# Frame_Diagram.net
KiCad netlist of a schematic drawn in EAGLE
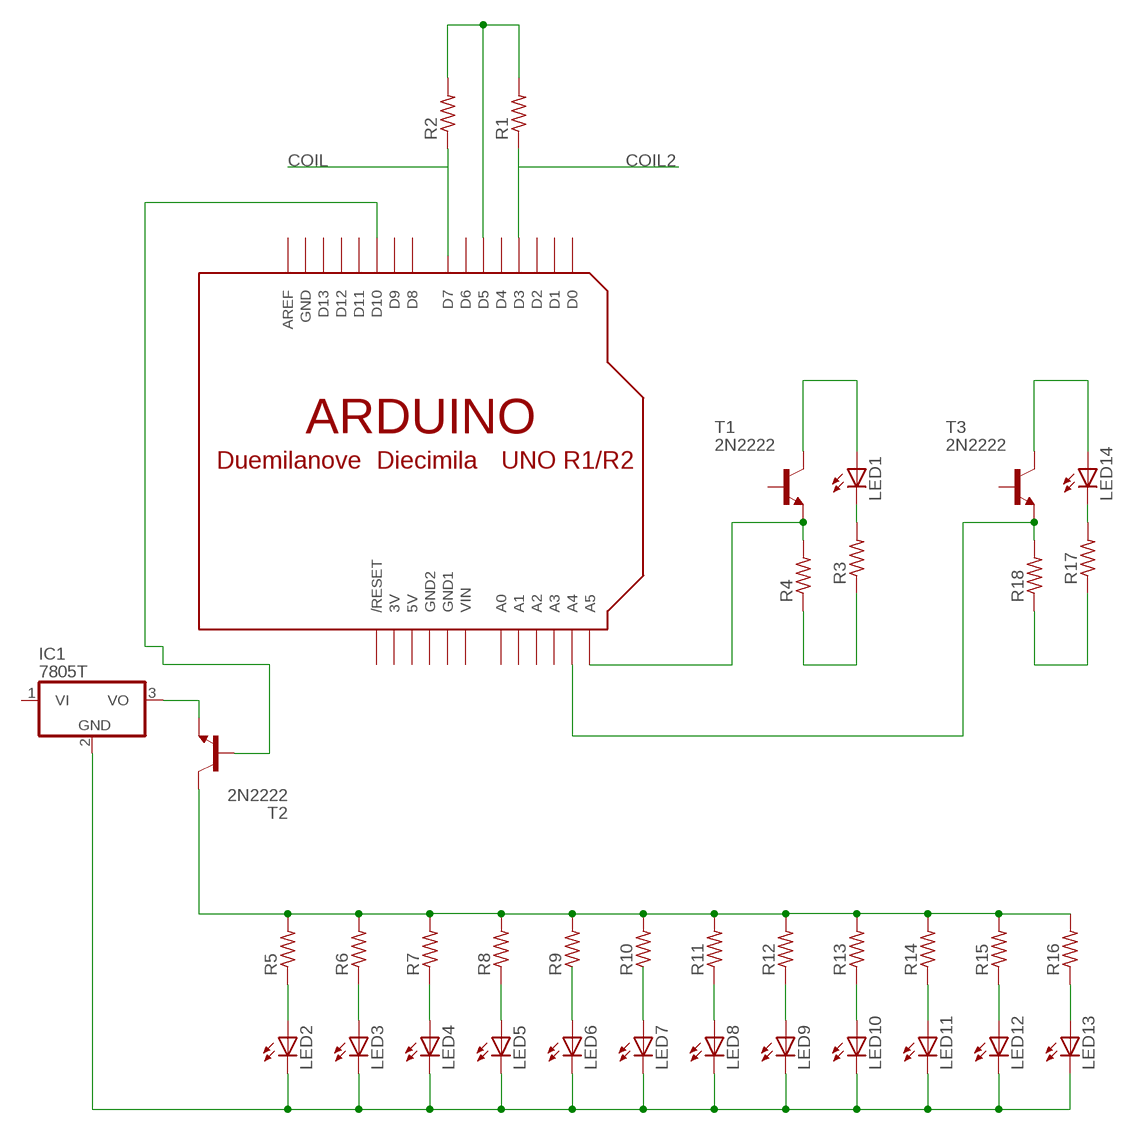
[diagram p0: schematic, sheet 1]

(export (version "E")
  (design (tool "Eeschema 10.0.6"))
  (components
    (comp (ref "IC1")
      (value "7805T")
      (footprint "eagle-import:TO220H")
      (libsource (lib "eagle-import") (part "78T05"))
    )
    (comp (ref "LED1")
      (value "LED")
      (footprint "eagle-import:SMARTLED-TTW")
      (libsource (lib "eagle-import") (part "LED"))
    )
    (comp (ref "LED2")
      (value "LEDLD260")
      (footprint "eagle-import:LD260")
      (libsource (lib "eagle-import") (part "LEDLD260"))
    )
    (comp (ref "LED3")
      (value "LEDLD260")
      (footprint "eagle-import:LD260")
      (libsource (lib "eagle-import") (part "LEDLD260"))
    )
    (comp (ref "LED4")
      (value "LEDLD260")
      (footprint "eagle-import:LD260")
      (libsource (lib "eagle-import") (part "LEDLD260"))
    )
    (comp (ref "LED5")
      (value "LEDLD260")
      (footprint "eagle-import:LD260")
      (libsource (lib "eagle-import") (part "LEDLD260"))
    )
    (comp (ref "LED6")
      (value "LEDLD260")
      (footprint "eagle-import:LD260")
      (libsource (lib "eagle-import") (part "LEDLD260"))
    )
    (comp (ref "LED7")
      (value "LEDLD260")
      (footprint "eagle-import:LD260")
      (libsource (lib "eagle-import") (part "LEDLD260"))
    )
    (comp (ref "LED8")
      (value "LEDLD260")
      (footprint "eagle-import:LD260")
      (libsource (lib "eagle-import") (part "LEDLD260"))
    )
    (comp (ref "LED9")
      (value "LEDLD260")
      (footprint "eagle-import:LD260")
      (libsource (lib "eagle-import") (part "LEDLD260"))
    )
    (comp (ref "LED10")
      (value "LEDLD260")
      (footprint "eagle-import:LD260")
      (libsource (lib "eagle-import") (part "LEDLD260"))
    )
    (comp (ref "LED11")
      (value "LEDLD260")
      (footprint "eagle-import:LD260")
      (libsource (lib "eagle-import") (part "LEDLD260"))
    )
    (comp (ref "LED12")
      (value "LEDLD260")
      (footprint "eagle-import:LD260")
      (libsource (lib "eagle-import") (part "LEDLD260"))
    )
    (comp (ref "LED13")
      (value "LEDLD260")
      (footprint "eagle-import:LD260")
      (libsource (lib "eagle-import") (part "LEDLD260"))
    )
    (comp (ref "LED14")
      (value "LED")
      (footprint "eagle-import:SMARTLED-TTW")
      (libsource (lib "eagle-import") (part "LED"))
    )
    (comp (ref "R1")
      (value "R-US_0204/7")
      (footprint "eagle-import:0204_7")
      (libsource (lib "eagle-import") (part "R-US_0204/7"))
    )
    (comp (ref "R2")
      (value "R-US_0204/7")
      (footprint "eagle-import:0204_7")
      (libsource (lib "eagle-import") (part "R-US_0204/7"))
    )
    (comp (ref "R3")
      (value "R-US_0204/7")
      (footprint "eagle-import:0204_7")
      (libsource (lib "eagle-import") (part "R-US_0204/7"))
    )
    (comp (ref "R4")
      (value "R-US_0204/7")
      (footprint "eagle-import:0204_7")
      (libsource (lib "eagle-import") (part "R-US_0204/7"))
    )
    (comp (ref "R5")
      (value "R-US_0204/5")
      (footprint "eagle-import:0204_5")
      (libsource (lib "eagle-import") (part "R-US_0204/5"))
    )
    (comp (ref "R6")
      (value "R-US_0204/5")
      (footprint "eagle-import:0204_5")
      (libsource (lib "eagle-import") (part "R-US_0204/5"))
    )
    (comp (ref "R7")
      (value "R-US_0204/5")
      (footprint "eagle-import:0204_5")
      (libsource (lib "eagle-import") (part "R-US_0204/5"))
    )
    (comp (ref "R8")
      (value "R-US_0204/5")
      (footprint "eagle-import:0204_5")
      (libsource (lib "eagle-import") (part "R-US_0204/5"))
    )
    (comp (ref "R9")
      (value "R-US_0204/5")
      (footprint "eagle-import:0204_5")
      (libsource (lib "eagle-import") (part "R-US_0204/5"))
    )
    (comp (ref "R10")
      (value "R-US_0204/5")
      (footprint "eagle-import:0204_5")
      (libsource (lib "eagle-import") (part "R-US_0204/5"))
    )
    (comp (ref "R11")
      (value "R-US_0204/5")
      (footprint "eagle-import:0204_5")
      (libsource (lib "eagle-import") (part "R-US_0204/5"))
    )
    (comp (ref "R12")
      (value "R-US_0204/5")
      (footprint "eagle-import:0204_5")
      (libsource (lib "eagle-import") (part "R-US_0204/5"))
    )
    (comp (ref "R13")
      (value "R-US_0204/5")
      (footprint "eagle-import:0204_5")
      (libsource (lib "eagle-import") (part "R-US_0204/5"))
    )
    (comp (ref "R14")
      (value "R-US_0204/5")
      (footprint "eagle-import:0204_5")
      (libsource (lib "eagle-import") (part "R-US_0204/5"))
    )
    (comp (ref "R15")
      (value "R-US_0204/5")
      (footprint "eagle-import:0204_5")
      (libsource (lib "eagle-import") (part "R-US_0204/5"))
    )
    (comp (ref "R16")
      (value "R-US_0204/5")
      (footprint "eagle-import:0204_5")
      (libsource (lib "eagle-import") (part "R-US_0204/5"))
    )
    (comp (ref "R17")
      (value "R-US_0204/7")
      (footprint "eagle-import:0204_7")
      (libsource (lib "eagle-import") (part "R-US_0204/7"))
    )
    (comp (ref "R18")
      (value "R-US_0204/7")
      (footprint "eagle-import:0204_7")
      (libsource (lib "eagle-import") (part "R-US_0204/7"))
    )
    (comp (ref "T1")
      (value "2N2222")
      (footprint "eagle-import:TO92-EBC-OVAL")
      (libsource (lib "eagle-import") (part "2N2222"))
    )
    (comp (ref "T2")
      (value "2N2222")
      (footprint "eagle-import:TO92-EBC-OVAL")
      (libsource (lib "eagle-import") (part "2N2222"))
    )
    (comp (ref "T3")
      (value "2N2222")
      (footprint "eagle-import:TO92-EBC-OVAL")
      (libsource (lib "eagle-import") (part "2N2222"))
    )
    (comp (ref "U$1")
      (value "ARDUINOUNO")
      (footprint "eagle-import:ARDUINO")
      (libsource (lib "eagle-import") (part "ARDUINOUNO"))
    )
  )
  (nets
    (net (code "1") (name "/3V") (class "Default")
      (node (ref "U$1") (pin "3V") (pinfunction "3V_3V") (pintype "power_in"))
    )
    (net (code "2") (name "/5V") (class "Default")
      (node (ref "U$1") (pin "5V") (pinfunction "5V_5V") (pintype "power_in"))
    )
    (net (code "3") (name "/COIL") (class "Default")
      (node (ref "R2") (pin "1") (pinfunction "1_1") (pintype "passive"))
    )
    (net (code "4") (name "/COIL2") (class "Default")
      (node (ref "R1") (pin "1") (pinfunction "1_1") (pintype "passive"))
      (node (ref "U$1") (pin "D3") (pinfunction "D3_D3") (pintype "bidirectional"))
    )
    (net (code "5") (name "/GND") (class "Default")
      (node (ref "U$1") (pin "GND") (pinfunction "GND_GND") (pintype "power_in"))
    )
    (net (code "6") (name "/GND1") (class "Default")
      (node (ref "U$1") (pin "GND1") (pinfunction "GND1_GND1") (pintype "power_in"))
    )
    (net (code "7") (name "/GND2") (class "Default")
      (node (ref "U$1") (pin "GND2") (pinfunction "GND2_GND2") (pintype "power_in"))
    )
    (net (code "8") (name "/VIN") (class "Default")
      (node (ref "U$1") (pin "VIN") (pinfunction "VIN_VIN") (pintype "power_in"))
    )
    (net (code "9") (name "Net-(IC1-GND)") (class "Default")
      (node (ref "IC1") (pin "2") (pinfunction "GND_2") (pintype "passive"))
      (node (ref "LED10") (pin "K") (pinfunction "C_K") (pintype "passive"))
      (node (ref "LED11") (pin "K") (pinfunction "C_K") (pintype "passive"))
      (node (ref "LED12") (pin "K") (pinfunction "C_K") (pintype "passive"))
      (node (ref "LED13") (pin "K") (pinfunction "C_K") (pintype "passive"))
      (node (ref "LED2") (pin "K") (pinfunction "C_K") (pintype "passive"))
      (node (ref "LED3") (pin "K") (pinfunction "C_K") (pintype "passive"))
      (node (ref "LED4") (pin "K") (pinfunction "C_K") (pintype "passive"))
      (node (ref "LED5") (pin "K") (pinfunction "C_K") (pintype "passive"))
      (node (ref "LED6") (pin "K") (pinfunction "C_K") (pintype "passive"))
      (node (ref "LED7") (pin "K") (pinfunction "C_K") (pintype "passive"))
      (node (ref "LED8") (pin "K") (pinfunction "C_K") (pintype "passive"))
      (node (ref "LED9") (pin "K") (pinfunction "C_K") (pintype "passive"))
    )
    (net (code "10") (name "Net-(IC1-VO)") (class "Default")
      (node (ref "IC1") (pin "3") (pinfunction "VO_3") (pintype "passive"))
      (node (ref "T2") (pin "E") (pinfunction "E_E") (pintype "passive"))
    )
    (net (code "11") (name "Net-(LED1-A)") (class "Default")
      (node (ref "LED1") (pin "A@1") (pinfunction "A_A@1") (pintype "passive"))
      (node (ref "T1") (pin "C") (pinfunction "C_C") (pintype "passive"))
    )
    (net (code "12") (name "Net-(LED1-C)") (class "Default")
      (node (ref "LED1") (pin "C@1") (pinfunction "C_C@1") (pintype "passive"))
      (node (ref "R3") (pin "2") (pinfunction "2_2") (pintype "passive"))
    )
    (net (code "13") (name "Net-(LED2-PadA)") (class "Default")
      (node (ref "LED2") (pin "A") (pinfunction "A_A") (pintype "passive"))
      (node (ref "R5") (pin "1") (pinfunction "1_1") (pintype "passive"))
    )
    (net (code "14") (name "Net-(LED3-PadA)") (class "Default")
      (node (ref "LED3") (pin "A") (pinfunction "A_A") (pintype "passive"))
      (node (ref "R6") (pin "1") (pinfunction "1_1") (pintype "passive"))
    )
    (net (code "15") (name "Net-(LED4-PadA)") (class "Default")
      (node (ref "LED4") (pin "A") (pinfunction "A_A") (pintype "passive"))
      (node (ref "R7") (pin "1") (pinfunction "1_1") (pintype "passive"))
    )
    (net (code "16") (name "Net-(LED5-PadA)") (class "Default")
      (node (ref "LED5") (pin "A") (pinfunction "A_A") (pintype "passive"))
      (node (ref "R8") (pin "1") (pinfunction "1_1") (pintype "passive"))
    )
    (net (code "17") (name "Net-(LED8-PadA)") (class "Default")
      (node (ref "LED8") (pin "A") (pinfunction "A_A") (pintype "passive"))
      (node (ref "R11") (pin "1") (pinfunction "1_1") (pintype "passive"))
    )
    (net (code "18") (name "Net-(LED9-PadA)") (class "Default")
      (node (ref "LED9") (pin "A") (pinfunction "A_A") (pintype "passive"))
      (node (ref "R12") (pin "1") (pinfunction "1_1") (pintype "passive"))
    )
    (net (code "19") (name "Net-(LED10-PadA)") (class "Default")
      (node (ref "LED10") (pin "A") (pinfunction "A_A") (pintype "passive"))
      (node (ref "R13") (pin "1") (pinfunction "1_1") (pintype "passive"))
    )
    (net (code "20") (name "Net-(LED11-PadA)") (class "Default")
      (node (ref "LED11") (pin "A") (pinfunction "A_A") (pintype "passive"))
      (node (ref "R14") (pin "1") (pinfunction "1_1") (pintype "passive"))
    )
    (net (code "21") (name "Net-(LED12-PadA)") (class "Default")
      (node (ref "LED12") (pin "A") (pinfunction "A_A") (pintype "passive"))
      (node (ref "R15") (pin "1") (pinfunction "1_1") (pintype "passive"))
    )
    (net (code "22") (name "Net-(LED13-PadA)") (class "Default")
      (node (ref "LED13") (pin "A") (pinfunction "A_A") (pintype "passive"))
      (node (ref "R16") (pin "1") (pinfunction "1_1") (pintype "passive"))
    )
    (net (code "23") (name "Net-(LED14-A)") (class "Default")
      (node (ref "LED14") (pin "A@1") (pinfunction "A_A@1") (pintype "passive"))
      (node (ref "T3") (pin "C") (pinfunction "C_C") (pintype "passive"))
    )
    (net (code "24") (name "Net-(LED14-C)") (class "Default")
      (node (ref "LED14") (pin "C@1") (pinfunction "C_C@1") (pintype "passive"))
      (node (ref "R17") (pin "2") (pinfunction "2_2") (pintype "passive"))
    )
    (net (code "25") (name "Net-(R1-Pad2)") (class "Default")
      (node (ref "R1") (pin "2") (pinfunction "2_2") (pintype "passive"))
      (node (ref "R2") (pin "2") (pinfunction "2_2") (pintype "passive"))
      (node (ref "U$1") (pin "D5") (pinfunction "D5_D5") (pintype "bidirectional"))
    )
    (net (code "26") (name "Net-(R3-Pad1)") (class "Default")
      (node (ref "R3") (pin "1") (pinfunction "1_1") (pintype "passive"))
      (node (ref "R4") (pin "1") (pinfunction "1_1") (pintype "passive"))
    )
    (net (code "27") (name "Net-(R4-Pad2)") (class "Default")
      (node (ref "R4") (pin "2") (pinfunction "2_2") (pintype "passive"))
      (node (ref "T1") (pin "E") (pinfunction "E_E") (pintype "passive"))
      (node (ref "U$1") (pin "A5") (pinfunction "A5_A5") (pintype "bidirectional"))
    )
    (net (code "28") (name "Net-(R10-Pad2)") (class "Default")
      (node (ref "R10") (pin "2") (pinfunction "2_2") (pintype "passive"))
      (node (ref "R11") (pin "2") (pinfunction "2_2") (pintype "passive"))
      (node (ref "R12") (pin "2") (pinfunction "2_2") (pintype "passive"))
      (node (ref "R13") (pin "2") (pinfunction "2_2") (pintype "passive"))
      (node (ref "R14") (pin "2") (pinfunction "2_2") (pintype "passive"))
      (node (ref "R15") (pin "2") (pinfunction "2_2") (pintype "passive"))
      (node (ref "R16") (pin "2") (pinfunction "2_2") (pintype "passive"))
      (node (ref "R5") (pin "2") (pinfunction "2_2") (pintype "passive"))
      (node (ref "R6") (pin "2") (pinfunction "2_2") (pintype "passive"))
      (node (ref "R7") (pin "2") (pinfunction "2_2") (pintype "passive"))
      (node (ref "R8") (pin "2") (pinfunction "2_2") (pintype "passive"))
      (node (ref "R9") (pin "2") (pinfunction "2_2") (pintype "passive"))
      (node (ref "T2") (pin "C") (pinfunction "C_C") (pintype "passive"))
    )
    (net (code "29") (name "Net-(R17-Pad1)") (class "Default")
      (node (ref "R17") (pin "1") (pinfunction "1_1") (pintype "passive"))
      (node (ref "R18") (pin "1") (pinfunction "1_1") (pintype "passive"))
    )
    (net (code "30") (name "Net-(R18-Pad2)") (class "Default")
      (node (ref "R18") (pin "2") (pinfunction "2_2") (pintype "passive"))
      (node (ref "T3") (pin "E") (pinfunction "E_E") (pintype "passive"))
      (node (ref "U$1") (pin "A4") (pinfunction "A4_A4") (pintype "bidirectional"))
    )
    (net (code "31") (name "Net-(T2-PadB)") (class "Default")
      (node (ref "T2") (pin "B") (pinfunction "B_B") (pintype "passive"))
      (node (ref "U$1") (pin "D10") (pinfunction "D10_D10") (pintype "bidirectional"))
    )
    (net (code "32") (name "unconnected-(IC1-VI-Pad1)") (class "Default")
      (node (ref "IC1") (pin "1") (pinfunction "VI_1") (pintype "input"))
    )
    (net (code "33") (name "unconnected-(LED6-PadA)") (class "Default")
      (node (ref "LED6") (pin "A") (pinfunction "A_A") (pintype "passive"))
    )
    (net (code "34") (name "unconnected-(LED7-PadA)") (class "Default")
      (node (ref "LED7") (pin "A") (pinfunction "A_A") (pintype "passive"))
    )
    (net (code "35") (name "unconnected-(R9-Pad1)") (class "Default")
      (node (ref "R9") (pin "1") (pinfunction "1_1") (pintype "passive"))
    )
    (net (code "36") (name "unconnected-(R10-Pad1)") (class "Default")
      (node (ref "R10") (pin "1") (pinfunction "1_1") (pintype "passive"))
    )
    (net (code "37") (name "unconnected-(T1-PadB)") (class "Default")
      (node (ref "T1") (pin "B") (pinfunction "B_B") (pintype "passive"))
    )
    (net (code "38") (name "unconnected-(T3-PadB)") (class "Default")
      (node (ref "T3") (pin "B") (pinfunction "B_B") (pintype "passive"))
    )
    (net (code "39") (name "unconnected-(U$1-PadA0)") (class "Default")
      (node (ref "U$1") (pin "A0") (pinfunction "A0_A0") (pintype "bidirectional"))
    )
    (net (code "40") (name "unconnected-(U$1-PadA1)") (class "Default")
      (node (ref "U$1") (pin "A1") (pinfunction "A1_A1") (pintype "bidirectional"))
    )
    (net (code "41") (name "unconnected-(U$1-PadA2)") (class "Default")
      (node (ref "U$1") (pin "A2") (pinfunction "A2_A2") (pintype "bidirectional"))
    )
    (net (code "42") (name "unconnected-(U$1-PadA3)") (class "Default")
      (node (ref "U$1") (pin "A3") (pinfunction "A3_A3") (pintype "bidirectional"))
    )
    (net (code "43") (name "unconnected-(U$1-PadAREF)") (class "Default")
      (node (ref "U$1") (pin "AREF") (pinfunction "AREF_AREF") (pintype "bidirectional"))
    )
    (net (code "44") (name "unconnected-(U$1-PadD0)") (class "Default")
      (node (ref "U$1") (pin "D0") (pinfunction "D0_D0") (pintype "bidirectional"))
    )
    (net (code "45") (name "unconnected-(U$1-PadD1)") (class "Default")
      (node (ref "U$1") (pin "D1") (pinfunction "D1_D1") (pintype "bidirectional"))
    )
    (net (code "46") (name "unconnected-(U$1-PadD2)") (class "Default")
      (node (ref "U$1") (pin "D2") (pinfunction "D2_D2") (pintype "bidirectional"))
    )
    (net (code "47") (name "unconnected-(U$1-PadD4)") (class "Default")
      (node (ref "U$1") (pin "D4") (pinfunction "D4_D4") (pintype "bidirectional"))
    )
    (net (code "48") (name "unconnected-(U$1-PadD6)") (class "Default")
      (node (ref "U$1") (pin "D6") (pinfunction "D6_D6") (pintype "bidirectional"))
    )
    (net (code "49") (name "unconnected-(U$1-PadD7)") (class "Default")
      (node (ref "U$1") (pin "D7") (pinfunction "D7_D7") (pintype "bidirectional"))
    )
    (net (code "50") (name "unconnected-(U$1-PadD8)") (class "Default")
      (node (ref "U$1") (pin "D8") (pinfunction "D8_D8") (pintype "bidirectional"))
    )
    (net (code "51") (name "unconnected-(U$1-PadD9)") (class "Default")
      (node (ref "U$1") (pin "D9") (pinfunction "D9_D9") (pintype "bidirectional"))
    )
    (net (code "52") (name "unconnected-(U$1-PadD11)") (class "Default")
      (node (ref "U$1") (pin "D11") (pinfunction "D11_D11") (pintype "bidirectional"))
    )
    (net (code "53") (name "unconnected-(U$1-PadD12)") (class "Default")
      (node (ref "U$1") (pin "D12") (pinfunction "D12_D12") (pintype "bidirectional"))
    )
    (net (code "54") (name "unconnected-(U$1-PadD13)") (class "Default")
      (node (ref "U$1") (pin "D13") (pinfunction "D13_D13") (pintype "bidirectional"))
    )
    (net (code "55") (name "unconnected-(U$1-{slash}RESET-PadRESET)") (class "Default")
      (node (ref "U$1") (pin "RESET") (pinfunction "/RESET_RESET") (pintype "bidirectional"))
    )
  )
)
